# Adafruit_Feather_M0_RFMxx.net
KiCad netlist of a schematic drawn in EAGLE
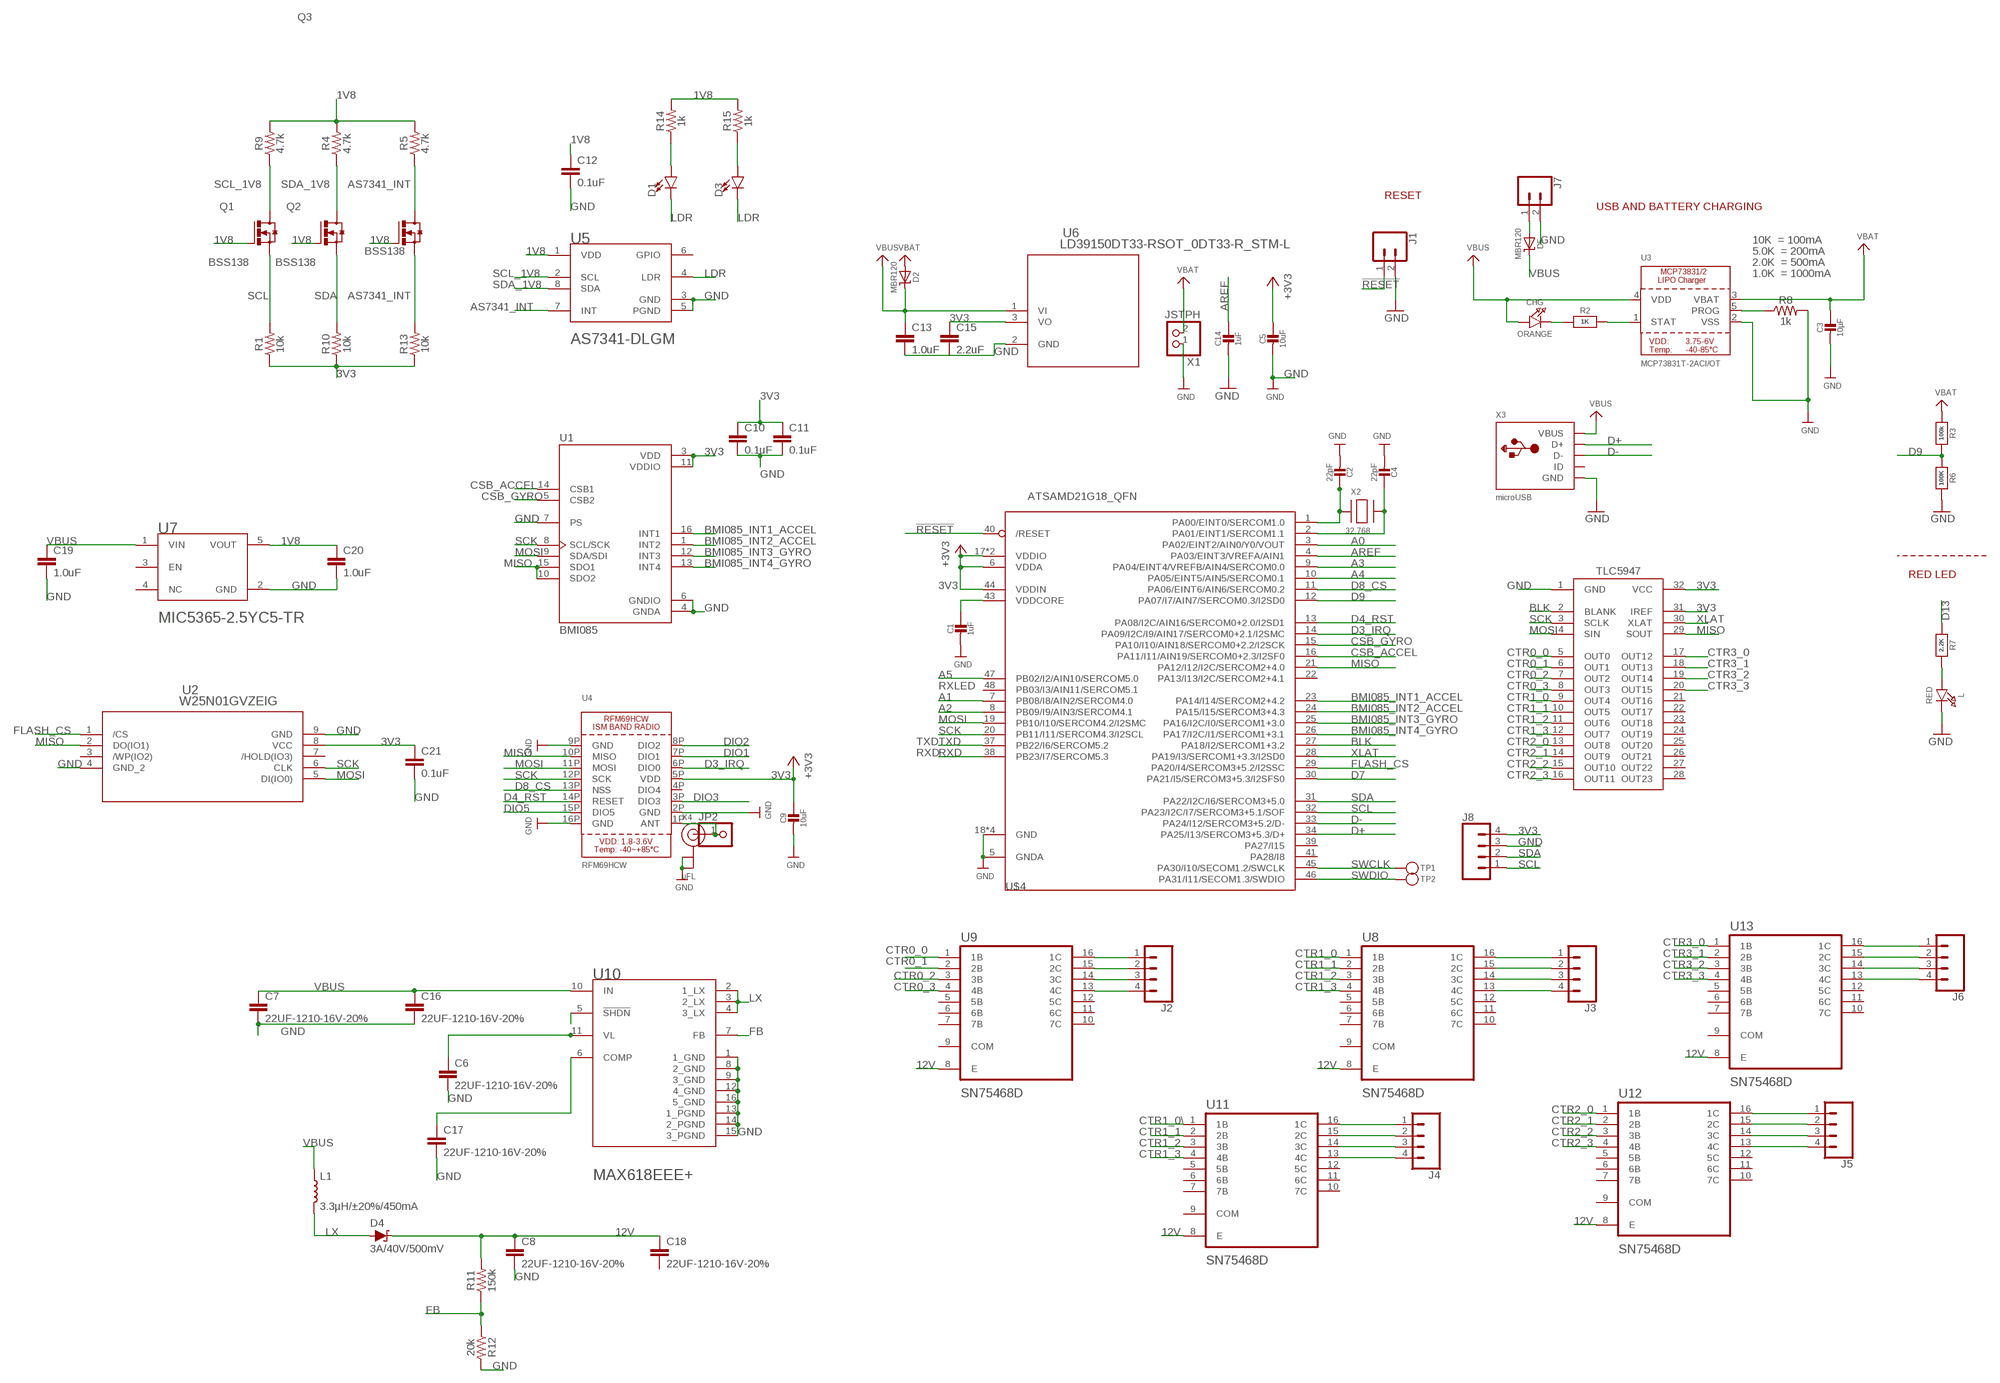
[diagram p0: schematic, sheet 1]

(export (version "E")
  (design (tool "Eeschema 10.0.6"))
  (components
    (comp (ref "C1")
      (value "1uF")
      (footprint "eagle-import:0603-NO")
      (libsource (lib "eagle-import") (part "CAP_CERAMIC0603_NO"))
    )
    (comp (ref "C2")
      (value "22pF")
      (footprint "eagle-import:0603-NO")
      (libsource (lib "eagle-import") (part "CAP_CERAMIC0603_NO"))
    )
    (comp (ref "C3")
      (value "10µF")
      (footprint "eagle-import:0805-NO")
      (libsource (lib "eagle-import") (part "CAP_CERAMIC0805-NOOUTLINE"))
    )
    (comp (ref "C4")
      (value "22pF")
      (footprint "eagle-import:0603-NO")
      (libsource (lib "eagle-import") (part "CAP_CERAMIC0603_NO"))
    )
    (comp (ref "C5")
      (value "10uF")
      (footprint "eagle-import:0805-NO")
      (libsource (lib "eagle-import") (part "CAP_CERAMIC0805-NOOUTLINE"))
    )
    (comp (ref "C6")
      (value "22UF-1210-16V-20%")
      (footprint "eagle-import:1210")
      (libsource (lib "eagle-import") (part "22UF-1210-16V-20%"))
    )
    (comp (ref "C7")
      (value "22UF-1210-16V-20%")
      (footprint "eagle-import:1210")
      (libsource (lib "eagle-import") (part "22UF-1210-16V-20%"))
    )
    (comp (ref "C8")
      (value "22UF-1210-16V-20%")
      (footprint "eagle-import:1210")
      (libsource (lib "eagle-import") (part "22UF-1210-16V-20%"))
    )
    (comp (ref "C9")
      (value "10uF")
      (footprint "eagle-import:0805-NO")
      (libsource (lib "eagle-import") (part "CAP_CERAMIC0805-NOOUTLINE"))
    )
    (comp (ref "C10")
      (value "0.1uF")
      (footprint "eagle-import:0603")
      (libsource (lib "eagle-import") (part "0.1UF-0603-25V-5%"))
    )
    (comp (ref "C11")
      (value "0.1uF")
      (footprint "eagle-import:0603")
      (libsource (lib "eagle-import") (part "0.1UF-0603-25V-5%"))
    )
    (comp (ref "C12")
      (value "0.1uF")
      (footprint "eagle-import:0603")
      (libsource (lib "eagle-import") (part "0.1UF-0603-25V-5%"))
    )
    (comp (ref "C13")
      (value "1.0uF")
      (footprint "eagle-import:0805")
      (libsource (lib "eagle-import") (part "1.0UF-0805-25V-(+80/-20%)"))
    )
    (comp (ref "C14")
      (value "1uF")
      (footprint "eagle-import:0603-NO")
      (libsource (lib "eagle-import") (part "CAP_CERAMIC0603_NO"))
    )
    (comp (ref "C15")
      (value "2.2uF")
      (footprint "eagle-import:0805")
      (libsource (lib "eagle-import") (part "2.2UF-0805-25V-(+80/-20%)"))
    )
    (comp (ref "C16")
      (value "22UF-1210-16V-20%")
      (footprint "eagle-import:1210")
      (libsource (lib "eagle-import") (part "22UF-1210-16V-20%"))
    )
    (comp (ref "C17")
      (value "22UF-1210-16V-20%")
      (footprint "eagle-import:1210")
      (libsource (lib "eagle-import") (part "22UF-1210-16V-20%"))
    )
    (comp (ref "C18")
      (value "22UF-1210-16V-20%")
      (footprint "eagle-import:1210")
      (libsource (lib "eagle-import") (part "22UF-1210-16V-20%"))
    )
    (comp (ref "C19")
      (value "1.0uF")
      (footprint "eagle-import:0805")
      (libsource (lib "eagle-import") (part "1.0UF-0805-25V-(+80/-20%)"))
    )
    (comp (ref "C20")
      (value "1.0uF")
      (footprint "eagle-import:0805")
      (libsource (lib "eagle-import") (part "1.0UF-0805-25V-(+80/-20%)"))
    )
    (comp (ref "C21")
      (value "0.1uF")
      (footprint "eagle-import:0603")
      (libsource (lib "eagle-import") (part "0.1UF-0603-100V-10%"))
    )
    (comp (ref "CHG")
      (value "ORANGE")
      (footprint "eagle-import:CHIPLED_0805_NOOUTLINE")
      (libsource (lib "eagle-import") (part "LED0805_NOOUTLINE"))
    )
    (comp (ref "D1")
      (value "LED1206")
      (footprint "eagle-import:LED-1206")
      (libsource (lib "eagle-import") (part "LED1206"))
    )
    (comp (ref "D2")
      (value "MBR120")
      (footprint "eagle-import:SOD-123")
      (libsource (lib "eagle-import") (part "DIODE-SCHOTTKYSOD-123"))
    )
    (comp (ref "D3")
      (value "LED1206")
      (footprint "eagle-import:LED-1206")
      (libsource (lib "eagle-import") (part "LED1206"))
    )
    (comp (ref "D4")
      (value "3A/40V/500mV")
      (footprint "eagle-import:SMA-DIODE")
      (libsource (lib "eagle-import") (part "DIODE-SCHOTTKY-B340A"))
    )
    (comp (ref "D5")
      (value "MBR120")
      (footprint "eagle-import:SOD-123")
      (libsource (lib "eagle-import") (part "DIODE-SCHOTTKYSOD-123"))
    )
    (comp (ref "IC1")
      (value "TLC5947-DAP")
      (footprint "eagle-import:HTSSOP32DAP")
      (fields (field (name "MF") "Texas Instruments") (field (name "MP") "TLC5947"))
      (libsource (lib "eagle-import") (part "TLC5947-DAP"))
    )
    (comp (ref "J1")
      (value "CONN_02")
      (footprint "eagle-import:1X02")
      (libsource (lib "eagle-import") (part "CONN_02"))
    )
    (comp (ref "J2")
      (value "CONN_04")
      (footprint "eagle-import:1X04")
      (libsource (lib "eagle-import") (part "CONN_04"))
    )
    (comp (ref "J3")
      (value "CONN_04")
      (footprint "eagle-import:1X04")
      (libsource (lib "eagle-import") (part "CONN_04"))
    )
    (comp (ref "J4")
      (value "CONN_04")
      (footprint "eagle-import:1X04")
      (libsource (lib "eagle-import") (part "CONN_04"))
    )
    (comp (ref "J5")
      (value "CONN_04")
      (footprint "eagle-import:1X04")
      (libsource (lib "eagle-import") (part "CONN_04"))
    )
    (comp (ref "J6")
      (value "CONN_04")
      (footprint "eagle-import:1X04")
      (libsource (lib "eagle-import") (part "CONN_04"))
    )
    (comp (ref "J7")
      (value "CONN_02")
      (footprint "eagle-import:1X02")
      (libsource (lib "eagle-import") (part "CONN_02"))
    )
    (comp (ref "J8")
      (value "CONN_04")
      (footprint "eagle-import:1X04")
      (libsource (lib "eagle-import") (part "CONN_04"))
    )
    (comp (ref "JP2")
      (value "HEADER-1X1ROUND")
      (footprint "eagle-import:1X01_ROUND")
      (libsource (lib "eagle-import") (part "HEADER-1X1ROUND"))
    )
    (comp (ref "L")
      (value "RED")
      (footprint "eagle-import:CHIPLED_0805_NOOUTLINE")
      (libsource (lib "eagle-import") (part "LED0805_NOOUTLINE"))
    )
    (comp (ref "L1")
      (value "3.3µH/±20%/450mA")
      (footprint "eagle-import:0805")
      (libsource (lib "eagle-import") (part "INDUCTOR-0805-3.3UH"))
    )
    (comp (ref "Q1")
      (value "BSS138")
      (footprint "eagle-import:SOT23-3")
      (fields
        (field (name "DIGIKEY_PART_NUMBER") "BSS138CT-ND")
        (field (name "MANUFACTURER") "ON Semiconductor")
        (field (name "CREATED_BY") "PCBLayout.com")
      )
      (libsource (lib "eagle-import") (part "BSS138"))
    )
    (comp (ref "Q2")
      (value "BSS138")
      (footprint "eagle-import:SOT23-3")
      (fields
        (field (name "DIGIKEY_PART_NUMBER") "BSS138CT-ND")
        (field (name "MANUFACTURER") "ON Semiconductor")
        (field (name "CREATED_BY") "PCBLayout.com")
      )
      (libsource (lib "eagle-import") (part "BSS138"))
    )
    (comp (ref "Q3")
      (value "BSS138")
      (footprint "eagle-import:SOT23-3")
      (fields
        (field (name "DIGIKEY_PART_NUMBER") "BSS138CT-ND")
        (field (name "MANUFACTURER") "ON Semiconductor")
        (field (name "CREATED_BY") "PCBLayout.com")
      )
      (libsource (lib "eagle-import") (part "BSS138"))
    )
    (comp (ref "R1")
      (value "10k")
      (footprint "eagle-import:0603")
      (libsource (lib "eagle-import") (part "10KOHM-0603-1/10W-1%"))
    )
    (comp (ref "R2")
      (value "1K")
      (footprint "eagle-import:0603-NO")
      (libsource (lib "eagle-import") (part "RESISTOR_0603_NOOUT"))
    )
    (comp (ref "R3")
      (value "100k")
      (footprint "eagle-import:0603-NO")
      (libsource (lib "eagle-import") (part "RESISTOR_0603_NOOUT"))
    )
    (comp (ref "R4")
      (value "4.7k")
      (footprint "eagle-import:0603")
      (libsource (lib "eagle-import") (part "4.7KOHM-0603-1/10W-1%"))
    )
    (comp (ref "R5")
      (value "4.7k")
      (footprint "eagle-import:0603")
      (libsource (lib "eagle-import") (part "4.7KOHM-0603-1/10W-1%"))
    )
    (comp (ref "R6")
      (value "100K")
      (footprint "eagle-import:0603-NO")
      (libsource (lib "eagle-import") (part "RESISTOR_0603_NOOUT"))
    )
    (comp (ref "R7")
      (value "2.2K")
      (footprint "eagle-import:0603-NO")
      (libsource (lib "eagle-import") (part "RESISTOR_0603_NOOUT"))
    )
    (comp (ref "R8")
      (value "1k")
      (footprint "eagle-import:0603")
      (libsource (lib "eagle-import") (part "1KOHM-0603-1/10W-1%"))
    )
    (comp (ref "R9")
      (value "4.7k")
      (footprint "eagle-import:0603")
      (libsource (lib "eagle-import") (part "4.7KOHM-0603-1/10W-1%"))
    )
    (comp (ref "R10")
      (value "10k")
      (footprint "eagle-import:0603")
      (libsource (lib "eagle-import") (part "10KOHM-0603-1/10W-1%"))
    )
    (comp (ref "R11")
      (value "150k")
      (footprint "eagle-import:0603")
      (libsource (lib "eagle-import") (part "150KOHM-0603-1/10W-1%"))
    )
    (comp (ref "R12")
      (value "20k")
      (footprint "eagle-import:0603")
      (libsource (lib "eagle-import") (part "20KOHM-0603-1/10W-1%"))
    )
    (comp (ref "R13")
      (value "10k")
      (footprint "eagle-import:0603")
      (libsource (lib "eagle-import") (part "10KOHM-0603-1/10W-1%"))
    )
    (comp (ref "R14")
      (value "1k")
      (footprint "eagle-import:0603")
      (libsource (lib "eagle-import") (part "1KOHM-0603-1/10W-1%"))
    )
    (comp (ref "R15")
      (value "1k")
      (footprint "eagle-import:0603")
      (libsource (lib "eagle-import") (part "1KOHM-0603-1/10W-1%"))
    )
    (comp (ref "TP1")
      (value "TESTPOINTROUND1.5MM")
      (footprint "eagle-import:TESTPOINT_ROUND_1.5MM")
      (libsource (lib "eagle-import") (part "TESTPOINTROUND1.5MM"))
    )
    (comp (ref "TP2")
      (value "TESTPOINTROUND1.5MM")
      (footprint "eagle-import:TESTPOINT_ROUND_1.5MM")
      (libsource (lib "eagle-import") (part "TESTPOINTROUND1.5MM"))
    )
    (comp (ref "U$4")
      (value "ATSAMD21G18_QFN")
      (footprint "eagle-import:TQFN48_7MM")
      (libsource (lib "eagle-import") (part "ATSAMD21J_QFN"))
    )
    (comp (ref "U1")
      (value "BMI085")
      (footprint "eagle-import:PQFN50P450X300X100-16N")
      (fields (field (name "MF") "Bosch Sensortec"))
      (libsource (lib "eagle-import") (part "BMI085"))
    )
    (comp (ref "U2")
      (value "W25N01GVZEIG")
      (footprint "eagle-import:WSON-8_6X5_WIN")
      (fields (field (name "COPYRIGHT") "Copyright (C) 2021 Ultra Librarian. All rights reserved."))
      (libsource (lib "eagle-import") (part "W25N01GVZEIG"))
    )
    (comp (ref "U3")
      (value "MCP73831T-2ACI/OT")
      (footprint "eagle-import:SOT23-5")
      (libsource (lib "eagle-import") (part "MCP73831/2"))
    )
    (comp (ref "U4")
      (value "RFM69HCW")
      (footprint "eagle-import:RFMHCW_SMT")
      (libsource (lib "eagle-import") (part "RFM69HCW_SMT"))
    )
    (comp (ref "U5")
      (value "AMS_AS7341-DLGMAMS_AS7341-DLGM_0_0")
      (footprint "eagle-import:AMS_AS7341-DLGM_0")
      (fields
        (field (name "DIGIKEY_PART_NUMBER") "AS7341-DLGMCT-ND")
        (field (name "MF") "ams")
        (field (name "MOUSER_PART_NUMBER") "985-AS7341-DLGM")
      )
      (libsource (lib "eagle-import") (part "AMS_AS7341-DLGMAMS_AS7341-DLGM_0_0"))
    )
    (comp (ref "U6")
      (value "LD39150DT33-RSOT_0DT33-R_STM-L")
      (footprint "eagle-import:SOT_0DT33-R_STM-L")
      (fields
        (field (name "MANUFACTURER_PART_NUMBER") "LD39150DT33-R")
        (field (name "COPYRIGHT") "Copyright (C) 2022 Ultra Librarian. All rights reserved.")
      )
      (libsource (lib "eagle-import") (part "LD39150DT33-RSOT_0DT33-R_STM-L"))
    )
    (comp (ref "U7")
      (value "MICROCHIP_MIC5365-2_5YC5-TRMICROCHIP_MIC5365-2_5YC5-TR_0_0")
      (footprint "eagle-import:MICROCHIP_MIC5365-2_5YC5-TR_0")
      (fields
        (field (name "DIGIKEY_PART_NUMBER") "576-3185-1-ND")
        (field (name "MF") "Microchip")
        (field (name "MOUSER_PART_NUMBER") "998-MIC5365-2.5YC5TR")
      )
      (libsource (lib "eagle-import") (part "MICROCHIP_MIC5365-2_5YC5-TRMICROCHIP_MIC5365-2_5YC5-TR_0_0"))
    )
    (comp (ref "U8")
      (value "SN75468D")
      (footprint "eagle-import:SOIC127P600X175-16N")
      (fields (field (name "MF") "Texas Instruments"))
      (libsource (lib "eagle-import") (part "SN75468D"))
    )
    (comp (ref "U9")
      (value "SN75468D")
      (footprint "eagle-import:SOIC127P600X175-16N")
      (fields (field (name "MF") "Texas Instruments"))
      (libsource (lib "eagle-import") (part "SN75468D"))
    )
    (comp (ref "U10")
      (value "MAXIM_MAX618EEE+MAXIM_MAX618EEE+_0_0")
      (footprint "eagle-import:MAXIM_MAX618EEE+_0")
      (fields
        (field (name "DIGIKEY_PART_NUMBER") "MAX618EEE+-ND")
        (field (name "MF") "Maxim")
        (field (name "MOUSER_PART_NUMBER") "700-MAX618EEE")
      )
      (libsource (lib "eagle-import") (part "MAXIM_MAX618EEE+MAXIM_MAX618EEE+_0_0"))
    )
    (comp (ref "U11")
      (value "SN75468D")
      (footprint "eagle-import:SOIC127P600X175-16N")
      (fields (field (name "MF") "Texas Instruments"))
      (libsource (lib "eagle-import") (part "SN75468D"))
    )
    (comp (ref "U12")
      (value "SN75468D")
      (footprint "eagle-import:SOIC127P600X175-16N")
      (fields (field (name "MF") "Texas Instruments"))
      (libsource (lib "eagle-import") (part "SN75468D"))
    )
    (comp (ref "U13")
      (value "SN75468D")
      (footprint "eagle-import:SOIC127P600X175-16N")
      (fields (field (name "MF") "Texas Instruments"))
      (libsource (lib "eagle-import") (part "SN75468D"))
    )
    (comp (ref "X1")
      (value "JSTPH")
      (footprint "eagle-import:JSTPH2")
      (libsource (lib "eagle-import") (part "CON_JST_PH_2PIN"))
    )
    (comp (ref "X2")
      (value "32.768")
      (footprint "eagle-import:XTAL3215")
      (libsource (lib "eagle-import") (part "XTAL-3.2X1.5"))
    )
    (comp (ref "X3")
      (value "microUSB")
      (footprint "eagle-import:4UCONN_20329_V2")
      (libsource (lib "eagle-import") (part "USB_MICRO_20329_V2"))
    )
    (comp (ref "X4")
      (value "uFL")
      (footprint "eagle-import:U.FL")
      (libsource (lib "eagle-import") (part "ANTENNA_U.FL"))
    )
  )
  (nets
    (net (code "1") (name "+3V3") (class "Default")
      (node (ref "C10") (pin "1") (pinfunction "1_1") (pintype "passive"))
      (node (ref "C11") (pin "1") (pinfunction "1_1") (pintype "passive"))
      (node (ref "C15") (pin "1") (pinfunction "1_1") (pintype "passive"))
      (node (ref "C21") (pin "1") (pinfunction "1_1") (pintype "passive"))
      (node (ref "C5") (pin "1") (pinfunction "1_1") (pintype "passive"))
      (node (ref "C9") (pin "1") (pinfunction "1_1") (pintype "passive"))
      (node (ref "IC1") (pin "31") (pinfunction "IREF_31") (pintype "bidirectional"))
      (node (ref "IC1") (pin "32") (pinfunction "VCC_32") (pintype "power_in"))
      (node (ref "J8") (pin "4") (pinfunction "4_4") (pintype "passive"))
      (node (ref "R1") (pin "1") (pinfunction "1_1") (pintype "passive"))
      (node (ref "R10") (pin "1") (pinfunction "1_1") (pintype "passive"))
      (node (ref "R13") (pin "1") (pinfunction "1_1") (pintype "passive"))
      (node (ref "U$4") (pin "17") (pinfunction "VDDIO_17") (pintype "power_in"))
      (node (ref "U$4") (pin "36") (pinfunction "VDDIO_36") (pintype "power_in"))
      (node (ref "U$4") (pin "44") (pinfunction "VDDIN_44") (pintype "power_in"))
      (node (ref "U$4") (pin "6") (pinfunction "VDDA_6") (pintype "power_in"))
      (node (ref "U1") (pin "11") (pinfunction "VDDIO_11") (pintype "power_in"))
      (node (ref "U1") (pin "3") (pinfunction "VDD_3") (pintype "power_in"))
      (node (ref "U2") (pin "8") (pinfunction "VCC_8") (pintype "power_in"))
      (node (ref "U4") (pin "5P") (pinfunction "VDD_5P") (pintype "power_in"))
      (node (ref "U6") (pin "3") (pinfunction "VO_3") (pintype "power_in"))
    )
    (net (code "2") (name "/1V8") (class "Default")
      (node (ref "C12") (pin "1") (pinfunction "1_1") (pintype "passive"))
      (node (ref "C20") (pin "1") (pinfunction "1_1") (pintype "passive"))
      (node (ref "Q1") (pin "1") (pinfunction "G_1") (pintype "passive"))
      (node (ref "Q2") (pin "1") (pinfunction "G_1") (pintype "passive"))
      (node (ref "Q3") (pin "1") (pinfunction "G_1") (pintype "passive"))
      (node (ref "R14") (pin "2") (pinfunction "2_2") (pintype "passive"))
      (node (ref "R15") (pin "2") (pinfunction "2_2") (pintype "passive"))
      (node (ref "R4") (pin "2") (pinfunction "2_2") (pintype "passive"))
      (node (ref "R5") (pin "2") (pinfunction "2_2") (pintype "passive"))
      (node (ref "R9") (pin "2") (pinfunction "2_2") (pintype "passive"))
      (node (ref "U5") (pin "1") (pinfunction "VDD_1") (pintype "power_in"))
      (node (ref "U7") (pin "5") (pinfunction "VOUT_5") (pintype "power_in"))
    )
    (net (code "3") (name "/12V") (class "Default")
      (node (ref "C18") (pin "1") (pinfunction "1_1") (pintype "passive"))
      (node (ref "C8") (pin "1") (pinfunction "1_1") (pintype "passive"))
      (node (ref "D4") (pin "C") (pinfunction "C_C") (pintype "passive"))
      (node (ref "R11") (pin "2") (pinfunction "2_2") (pintype "passive"))
      (node (ref "U11") (pin "8") (pinfunction "E_8") (pintype "bidirectional"))
      (node (ref "U12") (pin "8") (pinfunction "E_8") (pintype "bidirectional"))
      (node (ref "U13") (pin "8") (pinfunction "E_8") (pintype "bidirectional"))
      (node (ref "U8") (pin "8") (pinfunction "E_8") (pintype "bidirectional"))
      (node (ref "U9") (pin "8") (pinfunction "E_8") (pintype "bidirectional"))
    )
    (net (code "4") (name "/A0") (class "Default")
      (node (ref "U$4") (pin "3") (pinfunction "PA02/EINT2/AIN0/Y0/VOUT_3") (pintype "bidirectional"))
    )
    (net (code "5") (name "/A1") (class "Default")
      (node (ref "U$4") (pin "7") (pinfunction "PB08/I8/AIN2/SERCOM4.0_7") (pintype "bidirectional"))
    )
    (net (code "6") (name "/A2") (class "Default")
      (node (ref "U$4") (pin "8") (pinfunction "PB09/I9/AIN3/SERCOM4.1_8") (pintype "bidirectional"))
    )
    (net (code "7") (name "/A3") (class "Default")
      (node (ref "U$4") (pin "9") (pinfunction "PA04/EINT4/VREFB/AIN4/SERCOM0.0_9") (pintype "bidirectional"))
    )
    (net (code "8") (name "/A4") (class "Default")
      (node (ref "U$4") (pin "10") (pinfunction "PA05/EINT5/AIN5/SERCOM0.1_10") (pintype "bidirectional"))
    )
    (net (code "9") (name "/A5") (class "Default")
      (node (ref "U$4") (pin "47") (pinfunction "PB02/I2/AIN10/SERCOM5.0_47") (pintype "bidirectional"))
    )
    (net (code "10") (name "/AREF") (class "Default")
      (node (ref "C14") (pin "1") (pinfunction "1_1") (pintype "passive"))
      (node (ref "U$4") (pin "4") (pinfunction "PA03/EINT3/VREFA/AIN1_4") (pintype "bidirectional"))
    )
    (net (code "11") (name "/AS7341_INT") (class "Default")
      (node (ref "Q3") (pin "2") (pinfunction "S_2") (pintype "passive"))
      (node (ref "Q3") (pin "3") (pinfunction "D_3") (pintype "passive"))
      (node (ref "R13") (pin "2") (pinfunction "2_2") (pintype "passive"))
      (node (ref "R5") (pin "1") (pinfunction "1_1") (pintype "passive"))
      (node (ref "U5") (pin "7") (pinfunction "INT_7") (pintype "output"))
    )
    (net (code "12") (name "/BLK") (class "Default")
      (node (ref "IC1") (pin "2") (pinfunction "BLANK_2") (pintype "input"))
      (node (ref "U$4") (pin "27") (pinfunction "PA18/I2/SERCOM1+3.2_27") (pintype "bidirectional"))
    )
    (net (code "13") (name "/BMI085_INT1_ACCEL") (class "Default")
      (node (ref "U$4") (pin "23") (pinfunction "PA14/I14/SERCOM2+4.2_23") (pintype "bidirectional"))
      (node (ref "U1") (pin "16") (pinfunction "INT1_16") (pintype "bidirectional"))
    )
    (net (code "14") (name "/BMI085_INT2_ACCEL") (class "Default")
      (node (ref "U$4") (pin "24") (pinfunction "PA15/I15/SERCOM3+4.3_24") (pintype "bidirectional"))
      (node (ref "U1") (pin "1") (pinfunction "INT2_1") (pintype "bidirectional"))
    )
    (net (code "15") (name "/BMI085_INT3_GYRO") (class "Default")
      (node (ref "U$4") (pin "25") (pinfunction "PA16/I2C/I0/SERCOM1+3.0_25") (pintype "bidirectional"))
      (node (ref "U1") (pin "12") (pinfunction "INT3_12") (pintype "bidirectional"))
    )
    (net (code "16") (name "/BMI085_INT4_GYRO") (class "Default")
      (node (ref "U$4") (pin "26") (pinfunction "PA17/I2C/I1/SERCOM1+3.1_26") (pintype "bidirectional"))
      (node (ref "U1") (pin "13") (pinfunction "INT4_13") (pintype "bidirectional"))
    )
    (net (code "17") (name "/CSB_ACCEL") (class "Default")
      (node (ref "U$4") (pin "16") (pinfunction "PA11/I11/AIN19/SERCOM0+2.3/I2SF0_16") (pintype "bidirectional"))
      (node (ref "U1") (pin "14") (pinfunction "CSB1_14") (pintype "input"))
    )
    (net (code "18") (name "/CSB_GYRO") (class "Default")
      (node (ref "U$4") (pin "15") (pinfunction "PA10/I10/AIN18/SERCOM0+2.2/I2SCK_15") (pintype "bidirectional"))
      (node (ref "U1") (pin "5") (pinfunction "CSB2_5") (pintype "input"))
    )
    (net (code "19") (name "/CTR0_0") (class "Default")
      (node (ref "IC1") (pin "5") (pinfunction "OUT0_5") (pintype "open_collector"))
      (node (ref "U9") (pin "1") (pinfunction "1B_1") (pintype "input"))
    )
    (net (code "20") (name "/CTR0_1") (class "Default")
      (node (ref "IC1") (pin "6") (pinfunction "OUT1_6") (pintype "open_collector"))
      (node (ref "U9") (pin "2") (pinfunction "2B_2") (pintype "input"))
    )
    (net (code "21") (name "/CTR0_2") (class "Default")
      (node (ref "IC1") (pin "7") (pinfunction "OUT2_7") (pintype "open_collector"))
      (node (ref "U9") (pin "3") (pinfunction "3B_3") (pintype "input"))
    )
    (net (code "22") (name "/CTR0_3") (class "Default")
      (node (ref "IC1") (pin "8") (pinfunction "OUT3_8") (pintype "open_collector"))
      (node (ref "U9") (pin "4") (pinfunction "4B_4") (pintype "input"))
    )
    (net (code "23") (name "/CTR1_0") (class "Default")
      (node (ref "IC1") (pin "9") (pinfunction "OUT4_9") (pintype "open_collector"))
      (node (ref "U8") (pin "1") (pinfunction "1B_1") (pintype "input"))
    )
    (net (code "24") (name "/CTR1_0\\") (class "Default")
      (node (ref "U11") (pin "1") (pinfunction "1B_1") (pintype "input"))
    )
    (net (code "25") (name "/CTR1_1") (class "Default")
      (node (ref "IC1") (pin "10") (pinfunction "OUT5_10") (pintype "open_collector"))
      (node (ref "U11") (pin "2") (pinfunction "2B_2") (pintype "input"))
      (node (ref "U8") (pin "2") (pinfunction "2B_2") (pintype "input"))
    )
    (net (code "26") (name "/CTR1_2") (class "Default")
      (node (ref "IC1") (pin "11") (pinfunction "OUT6_11") (pintype "open_collector"))
      (node (ref "U11") (pin "3") (pinfunction "3B_3") (pintype "input"))
      (node (ref "U8") (pin "3") (pinfunction "3B_3") (pintype "input"))
    )
    (net (code "27") (name "/CTR1_3") (class "Default")
      (node (ref "IC1") (pin "12") (pinfunction "OUT7_12") (pintype "open_collector"))
      (node (ref "U11") (pin "4") (pinfunction "4B_4") (pintype "input"))
      (node (ref "U8") (pin "4") (pinfunction "4B_4") (pintype "input"))
    )
    (net (code "28") (name "/CTR2_0") (class "Default")
      (node (ref "IC1") (pin "13") (pinfunction "OUT8_13") (pintype "open_collector"))
      (node (ref "U12") (pin "1") (pinfunction "1B_1") (pintype "input"))
    )
    (net (code "29") (name "/CTR2_1") (class "Default")
      (node (ref "IC1") (pin "14") (pinfunction "OUT9_14") (pintype "open_collector"))
      (node (ref "U12") (pin "2") (pinfunction "2B_2") (pintype "input"))
    )
    (net (code "30") (name "/CTR2_2") (class "Default")
      (node (ref "IC1") (pin "15") (pinfunction "OUT10_15") (pintype "open_collector"))
      (node (ref "U12") (pin "3") (pinfunction "3B_3") (pintype "input"))
    )
    (net (code "31") (name "/CTR2_3") (class "Default")
      (node (ref "IC1") (pin "16") (pinfunction "OUT11_16") (pintype "open_collector"))
      (node (ref "U12") (pin "4") (pinfunction "4B_4") (pintype "input"))
    )
    (net (code "32") (name "/CTR3_0") (class "Default")
      (node (ref "IC1") (pin "17") (pinfunction "OUT12_17") (pintype "open_collector"))
      (node (ref "U13") (pin "1") (pinfunction "1B_1") (pintype "input"))
    )
    (net (code "33") (name "/CTR3_1") (class "Default")
      (node (ref "IC1") (pin "18") (pinfunction "OUT13_18") (pintype "open_collector"))
      (node (ref "U13") (pin "2") (pinfunction "2B_2") (pintype "input"))
    )
    (net (code "34") (name "/CTR3_2") (class "Default")
      (node (ref "IC1") (pin "19") (pinfunction "OUT14_19") (pintype "open_collector"))
      (node (ref "U13") (pin "3") (pinfunction "3B_3") (pintype "input"))
    )
    (net (code "35") (name "/CTR3_3") (class "Default")
      (node (ref "IC1") (pin "20") (pinfunction "OUT15_20") (pintype "open_collector"))
      (node (ref "U13") (pin "4") (pinfunction "4B_4") (pintype "input"))
    )
    (net (code "36") (name "/D+") (class "Default")
      (node (ref "U$4") (pin "34") (pinfunction "PA25/I13/SERCOM3+5.3/D+_34") (pintype "bidirectional"))
      (node (ref "X3") (pin "D+") (pinfunction "D+_D+") (pintype "bidirectional"))
    )
    (net (code "37") (name "/D-") (class "Default")
      (node (ref "U$4") (pin "33") (pinfunction "PA24/I12/SERCOM3+5.2/D-_33") (pintype "bidirectional"))
      (node (ref "X3") (pin "D-") (pinfunction "D-_D-") (pintype "bidirectional"))
    )
    (net (code "38") (name "/D3_IRQ") (class "Default")
      (node (ref "U$4") (pin "14") (pinfunction "PA09/I2C/I9/AIN17/SERCOM0+2.1/I2SMC_14") (pintype "bidirectional"))
      (node (ref "U4") (pin "6P") (pinfunction "DIO0_6P") (pintype "bidirectional"))
    )
    (net (code "39") (name "/D4_RST") (class "Default")
      (node (ref "U$4") (pin "13") (pinfunction "PA08/I2C/AIN16/SERCOM0+2.0/I2SD1_13") (pintype "bidirectional"))
      (node (ref "U4") (pin "14P") (pinfunction "RESET_14P") (pintype "input"))
    )
    (net (code "40") (name "/D7") (class "Default")
      (node (ref "U$4") (pin "30") (pinfunction "PA21/I5/SERCOM3+5.3/I2SFS0_30") (pintype "bidirectional"))
    )
    (net (code "41") (name "/D8_CS") (class "Default")
      (node (ref "U$4") (pin "11") (pinfunction "PA06/EINT6/AIN6/SERCOM0.2_11") (pintype "bidirectional"))
      (node (ref "U4") (pin "13P") (pinfunction "NSS_13P") (pintype "input"))
    )
    (net (code "42") (name "/D9") (class "Default")
      (node (ref "R3") (pin "2") (pinfunction "2_2") (pintype "passive"))
      (node (ref "R6") (pin "1") (pinfunction "1_1") (pintype "passive"))
      (node (ref "U$4") (pin "12") (pinfunction "PA07/I7/AIN7/SERCOM0.3/I2SD0_12") (pintype "bidirectional"))
    )
    (net (code "43") (name "/D13") (class "Default")
      (node (ref "R7") (pin "1") (pinfunction "1_1") (pintype "passive"))
    )
    (net (code "44") (name "/DIO1") (class "Default")
      (node (ref "U4") (pin "7P") (pinfunction "DIO1_7P") (pintype "bidirectional"))
    )
    (net (code "45") (name "/DIO2") (class "Default")
      (node (ref "U4") (pin "8P") (pinfunction "DIO2_8P") (pintype "bidirectional"))
    )
    (net (code "46") (name "/DIO3") (class "Default")
      (node (ref "U4") (pin "3P") (pinfunction "DIO3_3P") (pintype "bidirectional"))
    )
    (net (code "47") (name "/DIO5") (class "Default")
      (node (ref "U4") (pin "15P") (pinfunction "DIO5_15P") (pintype "bidirectional"))
    )
    (net (code "48") (name "/FB") (class "Default")
      (node (ref "R11") (pin "1") (pinfunction "1_1") (pintype "passive"))
      (node (ref "R12") (pin "1") (pinfunction "1_1") (pintype "passive"))
      (node (ref "U10") (pin "7") (pinfunction "FB_7") (pintype "passive"))
    )
    (net (code "49") (name "/FLASH_CS") (class "Default")
      (node (ref "U$4") (pin "29") (pinfunction "PA20/I4/SERCOM3+5.2/I2SSC_29") (pintype "bidirectional"))
      (node (ref "U2") (pin "1") (pinfunction "/CS_1") (pintype "input"))
    )
    (net (code "50") (name "/LDR") (class "Default")
      (node (ref "D1") (pin "C") (pinfunction "C_C") (pintype "passive"))
      (node (ref "D3") (pin "C") (pinfunction "C_C") (pintype "passive"))
      (node (ref "U5") (pin "4") (pinfunction "LDR_4") (pintype "input"))
    )
    (net (code "51") (name "/LX") (class "Default")
      (node (ref "D4") (pin "A") (pinfunction "A_A") (pintype "passive"))
      (node (ref "L1") (pin "2") (pinfunction "2_2") (pintype "passive"))
      (node (ref "U10") (pin "2") (pinfunction "1_LX_2") (pintype "passive"))
      (node (ref "U10") (pin "3") (pinfunction "2_LX_3") (pintype "passive"))
      (node (ref "U10") (pin "4") (pinfunction "3_LX_4") (pintype "passive"))
    )
    (net (code "52") (name "/MISO") (class "Default")
      (node (ref "IC1") (pin "29") (pinfunction "SOUT_29") (pintype "output"))
      (node (ref "U$4") (pin "21") (pinfunction "PA12/I12/I2C/SERCOM2+4.0_21") (pintype "bidirectional"))
      (node (ref "U1") (pin "10") (pinfunction "SDO2_10") (pintype "output"))
      (node (ref "U1") (pin "15") (pinfunction "SDO1_15") (pintype "output"))
      (node (ref "U2") (pin "2") (pinfunction "DO(IO1)_2") (pintype "bidirectional"))
      (node (ref "U4") (pin "10P") (pinfunction "MISO_10P") (pintype "output"))
    )
    (net (code "53") (name "/MOSI") (class "Default")
      (node (ref "IC1") (pin "4") (pinfunction "SIN_4") (pintype "input"))
      (node (ref "U$4") (pin "19") (pinfunction "PB10/I10/SERCOM4.2/I2SMC_19") (pintype "bidirectional"))
      (node (ref "U1") (pin "9") (pinfunction "SDA/SDI_9") (pintype "bidirectional"))
      (node (ref "U2") (pin "5") (pinfunction "DI(IO0)_5") (pintype "bidirectional"))
      (node (ref "U4") (pin "11P") (pinfunction "MOSI_11P") (pintype "input"))
    )
    (net (code "54") (name "/RXD") (class "Default")
      (node (ref "U$4") (pin "38") (pinfunction "PB23/I7/SERCOM5.3_38") (pintype "bidirectional"))
    )
    (net (code "55") (name "/SCK") (class "Default")
      (node (ref "IC1") (pin "3") (pinfunction "SCLK_3") (pintype "input"))
      (node (ref "U$4") (pin "20") (pinfunction "PB11/I11/SERCOM4.3/I2SCL_20") (pintype "bidirectional"))
      (node (ref "U1") (pin "8") (pinfunction "SCL/SCK_8") (pintype "input"))
      (node (ref "U2") (pin "6") (pinfunction "CLK_6") (pintype "input"))
      (node (ref "U4") (pin "12P") (pinfunction "SCK_12P") (pintype "input"))
    )
    (net (code "56") (name "/SCL") (class "Default")
      (node (ref "J8") (pin "1") (pinfunction "1_1") (pintype "passive"))
      (node (ref "Q1") (pin "2") (pinfunction "S_2") (pintype "passive"))
      (node (ref "R1") (pin "2") (pinfunction "2_2") (pintype "passive"))
      (node (ref "U$4") (pin "32") (pinfunction "PA23/I2C/I7/SERCOM3+5.1/SOF_32") (pintype "bidirectional"))
    )
    (net (code "57") (name "/SCL_1V8") (class "Default")
      (node (ref "Q1") (pin "3") (pinfunction "D_3") (pintype "passive"))
      (node (ref "R9") (pin "1") (pinfunction "1_1") (pintype "passive"))
      (node (ref "U5") (pin "2") (pinfunction "SCL_2") (pintype "bidirectional"))
    )
    (net (code "58") (name "/SDA") (class "Default")
      (node (ref "J8") (pin "2") (pinfunction "2_2") (pintype "passive"))
      (node (ref "Q2") (pin "2") (pinfunction "S_2") (pintype "passive"))
      (node (ref "R10") (pin "2") (pinfunction "2_2") (pintype "passive"))
      (node (ref "U$4") (pin "31") (pinfunction "PA22/I2C/I6/SERCOM3+5.0_31") (pintype "bidirectional"))
    )
    (net (code "59") (name "/SDA_1V8") (class "Default")
      (node (ref "Q2") (pin "3") (pinfunction "D_3") (pintype "passive"))
      (node (ref "R4") (pin "1") (pinfunction "1_1") (pintype "passive"))
      (node (ref "U5") (pin "8") (pinfunction "SDA_8") (pintype "bidirectional"))
    )
    (net (code "60") (name "/SWCLK") (class "Default")
      (node (ref "TP1") (pin "P$1") (pinfunction "P$1_P$1") (pintype "bidirectional"))
      (node (ref "U$4") (pin "45") (pinfunction "PA30/I10/SECOM1.2/SWCLK_45") (pintype "bidirectional"))
    )
    (net (code "61") (name "/SWDIO") (class "Default")
      (node (ref "TP2") (pin "P$1") (pinfunction "P$1_P$1") (pintype "bidirectional"))
      (node (ref "U$4") (pin "46") (pinfunction "PA31/I11/SECOM1.3/SWDIO_46") (pintype "bidirectional"))
    )
    (net (code "62") (name "/TXD") (class "Default")
      (node (ref "U$4") (pin "37") (pinfunction "PB22/I6/SERCOM5.2_37") (pintype "bidirectional"))
    )
    (net (code "63") (name "/XLAT") (class "Default")
      (node (ref "IC1") (pin "30") (pinfunction "XLAT_30") (pintype "input"))
      (node (ref "U$4") (pin "28") (pinfunction "PA19/I3/SERCOM1+3.3/I2SD0_28") (pintype "bidirectional"))
    )
    (net (code "64") (name "/~{RESET}") (class "Default")
      (node (ref "J1") (pin "1") (pinfunction "1_1") (pintype "passive"))
      (node (ref "U$4") (pin "40") (pinfunction "/RESET_40") (pintype "bidirectional"))
    )
    (net (code "65") (name "GND") (class "Default")
      (node (ref "C1") (pin "2") (pinfunction "2_2") (pintype "passive"))
      (node (ref "C10") (pin "2") (pinfunction "2_2") (pintype "passive"))
      (node (ref "C11") (pin "2") (pinfunction "2_2") (pintype "passive"))
      (node (ref "C12") (pin "2") (pinfunction "2_2") (pintype "passive"))
      (node (ref "C13") (pin "2") (pinfunction "2_2") (pintype "passive"))
      (node (ref "C14") (pin "2") (pinfunction "2_2") (pintype "passive"))
      (node (ref "C15") (pin "2") (pinfunction "2_2") (pintype "passive"))
      (node (ref "C16") (pin "2") (pinfunction "2_2") (pintype "passive"))
      (node (ref "C17") (pin "2") (pinfunction "2_2") (pintype "passive"))
      (node (ref "C19") (pin "2") (pinfunction "2_2") (pintype "passive"))
      (node (ref "C2") (pin "2") (pinfunction "2_2") (pintype "passive"))
      (node (ref "C20") (pin "2") (pinfunction "2_2") (pintype "passive"))
      (node (ref "C21") (pin "2") (pinfunction "2_2") (pintype "passive"))
      (node (ref "C3") (pin "2") (pinfunction "2_2") (pintype "passive"))
      (node (ref "C4") (pin "2") (pinfunction "2_2") (pintype "passive"))
      (node (ref "C5") (pin "2") (pinfunction "2_2") (pintype "passive"))
      (node (ref "C6") (pin "2") (pinfunction "2_2") (pintype "passive"))
      (node (ref "C7") (pin "2") (pinfunction "2_2") (pintype "passive"))
      (node (ref "C8") (pin "2") (pinfunction "2_2") (pintype "passive"))
      (node (ref "C9") (pin "2") (pinfunction "2_2") (pintype "passive"))
      (node (ref "IC1") (pin "1") (pinfunction "GND_1") (pintype "power_in"))
      (node (ref "J1") (pin "2") (pinfunction "2_2") (pintype "passive"))
      (node (ref "J7") (pin "2") (pinfunction "2_2") (pintype "passive"))
      (node (ref "J8") (pin "3") (pinfunction "3_3") (pintype "passive"))
      (node (ref "L") (pin "C") (pinfunction "C_C") (pintype "passive"))
      (node (ref "R12") (pin "2") (pinfunction "2_2") (pintype "passive"))
      (node (ref "R6") (pin "2") (pinfunction "2_2") (pintype "passive"))
      (node (ref "R8") (pin "2") (pinfunction "2_2") (pintype "passive"))
      (node (ref "U$4") (pin "18") (pinfunction "GND_18") (pintype "power_in"))
      (node (ref "U$4") (pin "35") (pinfunction "GND_35") (pintype "power_in"))
      (node (ref "U$4") (pin "42") (pinfunction "GND_42") (pintype "power_in"))
      (node (ref "U$4") (pin "5") (pinfunction "GNDA_5") (pintype "power_in"))
      (node (ref "U$4") (pin "THERMAL") (pinfunction "GND_THERMAL") (pintype "power_in"))
      (node (ref "U1") (pin "4") (pinfunction "GNDA_4") (pintype "power_in"))
      (node (ref "U1") (pin "6") (pinfunction "GNDIO_6") (pintype "power_in"))
      (node (ref "U1") (pin "7") (pinfunction "PS_7") (pintype "input"))
      (node (ref "U10") (pin "1") (pinfunction "1_GND_1") (pintype "power_in"))
      (node (ref "U10") (pin "12") (pinfunction "4_GND_12") (pintype "power_in"))
      (node (ref "U10") (pin "13") (pinfunction "1_PGND_13") (pintype "power_in"))
      (node (ref "U10") (pin "14") (pinfunction "2_PGND_14") (pintype "power_in"))
      (node (ref "U10") (pin "15") (pinfunction "3_PGND_15") (pintype "power_in"))
      (node (ref "U10") (pin "16") (pinfunction "5_GND_16") (pintype "power_in"))
      (node (ref "U10") (pin "8") (pinfunction "2_GND_8") (pintype "power_in"))
      (node (ref "U10") (pin "9") (pinfunction "3_GND_9") (pintype "power_in"))
      (node (ref "U2") (pin "4") (pinfunction "GND_2_4") (pintype "passive"))
      (node (ref "U2") (pin "9") (pinfunction "GND_9") (pintype "passive"))
      (node (ref "U3") (pin "2") (pinfunction "VSS_2") (pintype "power_in"))
      (node (ref "U4") (pin "16P") (pinfunction "GND_16P") (pintype "power_in"))
      (node (ref "U4") (pin "2P") (pinfunction "GND_2P") (pintype "power_in"))
      (node (ref "U4") (pin "9P") (pinfunction "GND_9P") (pintype "power_in"))
      (node (ref "U5") (pin "3") (pinfunction "GND_3") (pintype "power_in"))
      (node (ref "U5") (pin "5") (pinfunction "PGND_5") (pintype "power_in"))
      (node (ref "U6") (pin "2") (pinfunction "GND_2") (pintype "passive"))
      (node (ref "U7") (pin "2") (pinfunction "GND_2") (pintype "power_in"))
      (node (ref "X1") (pin "1") (pinfunction "1_1") (pintype "passive"))
      (node (ref "X3") (pin "BASE@1") (pinfunction "GND_BASE@1") (pintype "power_in"))
      (node (ref "X3") (pin "BASE@2") (pinfunction "GND_BASE@2") (pintype "power_in"))
      (node (ref "X3") (pin "GND") (pinfunction "GND_GND") (pintype "power_in"))
      (node (ref "X3") (pin "SPRT@1") (pinfunction "GND_SPRT@1") (pintype "power_in"))
      (node (ref "X3") (pin "SPRT@2") (pinfunction "GND_SPRT@2") (pintype "power_in"))
      (node (ref "X3") (pin "SPRT@3") (pinfunction "GND_SPRT@3") (pintype "power_in"))
      (node (ref "X3") (pin "SPRT@4") (pinfunction "GND_SPRT@4") (pintype "power_in"))
      (node (ref "X4") (pin "1") (pinfunction "GND_1") (pintype "passive"))
      (node (ref "X4") (pin "2") (pinfunction "GND_2") (pintype "passive"))
    )
    (net (code "66") (name "Net-(CHG-PadC)") (class "Default")
      (node (ref "CHG") (pin "C") (pinfunction "C_C") (pintype "passive"))
      (node (ref "R2") (pin "1") (pinfunction "1_1") (pintype "passive"))
    )
    (net (code "67") (name "Net-(D1-PadA)") (class "Default")
      (node (ref "D1") (pin "A") (pinfunction "A_A") (pintype "passive"))
      (node (ref "R14") (pin "1") (pinfunction "1_1") (pintype "passive"))
    )
    (net (code "68") (name "Net-(D3-PadA)") (class "Default")
      (node (ref "D3") (pin "A") (pinfunction "A_A") (pintype "passive"))
      (node (ref "R15") (pin "1") (pinfunction "1_1") (pintype "passive"))
    )
    (net (code "69") (name "Net-(D5-PadA)") (class "Default")
      (node (ref "D5") (pin "A") (pinfunction "A_A") (pintype "passive"))
      (node (ref "J7") (pin "1") (pinfunction "1_1") (pintype "passive"))
    )
    (net (code "70") (name "Net-(L-PadA)") (class "Default")
      (node (ref "L") (pin "A") (pinfunction "A_A") (pintype "passive"))
      (node (ref "R7") (pin "2") (pinfunction "2_2") (pintype "passive"))
    )
    (net (code "71") (name "Net-(U$4-PA00{slash}EINT0{slash}SERCOM1.0)") (class "Default")
      (node (ref "C2") (pin "1") (pinfunction "1_1") (pintype "passive"))
      (node (ref "U$4") (pin "1") (pinfunction "PA00/EINT0/SERCOM1.0_1") (pintype "bidirectional"))
      (node (ref "X2") (pin "P$1") (pinfunction "P$1_P$1") (pintype "bidirectional"))
    )
    (net (code "72") (name "Net-(U$4-PA01{slash}EINT1{slash}SERCOM1.1)") (class "Default")
      (node (ref "C4") (pin "1") (pinfunction "1_1") (pintype "passive"))
      (node (ref "U$4") (pin "2") (pinfunction "PA01/EINT1/SERCOM1.1_2") (pintype "bidirectional"))
      (node (ref "X2") (pin "P$2") (pinfunction "P$2_P$2") (pintype "bidirectional"))
    )
    (net (code "73") (name "Net-(U$4-VDDCORE)") (class "Default")
      (node (ref "C1") (pin "1") (pinfunction "1_1") (pintype "passive"))
      (node (ref "U$4") (pin "43") (pinfunction "VDDCORE_43") (pintype "power_in"))
    )
    (net (code "74") (name "Net-(U3-PROG)") (class "Default")
      (node (ref "R8") (pin "1") (pinfunction "1_1") (pintype "passive"))
      (node (ref "U3") (pin "5") (pinfunction "PROG_5") (pintype "input"))
    )
    (net (code "75") (name "Net-(U3-STAT)") (class "Default")
      (node (ref "R2") (pin "2") (pinfunction "2_2") (pintype "passive"))
      (node (ref "U3") (pin "1") (pinfunction "STAT_1") (pintype "output"))
    )
    (net (code "76") (name "Net-(U4-ANT)") (class "Default")
      (node (ref "JP2") (pin "1") (pinfunction "1_1") (pintype "passive"))
      (node (ref "U4") (pin "1P") (pinfunction "ANT_1P") (pintype "bidirectional"))
      (node (ref "X4") (pin "3") (pinfunction "SIGNAL_3") (pintype "passive"))
    )
    (net (code "77") (name "Net-(U8-1C)") (class "Default")
      (node (ref "J3") (pin "1") (pinfunction "1_1") (pintype "passive"))
      (node (ref "U8") (pin "16") (pinfunction "1C_16") (pintype "output"))
    )
    (net (code "78") (name "Net-(U8-2C)") (class "Default")
      (node (ref "J3") (pin "2") (pinfunction "2_2") (pintype "passive"))
      (node (ref "U8") (pin "15") (pinfunction "2C_15") (pintype "output"))
    )
    (net (code "79") (name "Net-(U8-3C)") (class "Default")
      (node (ref "J3") (pin "3") (pinfunction "3_3") (pintype "passive"))
      (node (ref "U8") (pin "14") (pinfunction "3C_14") (pintype "output"))
    )
    (net (code "80") (name "Net-(U8-4C)") (class "Default")
      (node (ref "J3") (pin "4") (pinfunction "4_4") (pintype "passive"))
      (node (ref "U8") (pin "13") (pinfunction "4C_13") (pintype "output"))
    )
    (net (code "81") (name "Net-(U9-1C)") (class "Default")
      (node (ref "J2") (pin "1") (pinfunction "1_1") (pintype "passive"))
      (node (ref "U9") (pin "16") (pinfunction "1C_16") (pintype "output"))
    )
    (net (code "82") (name "Net-(U9-2C)") (class "Default")
      (node (ref "J2") (pin "2") (pinfunction "2_2") (pintype "passive"))
      (node (ref "U9") (pin "15") (pinfunction "2C_15") (pintype "output"))
    )
    (net (code "83") (name "Net-(U9-3C)") (class "Default")
      (node (ref "J2") (pin "3") (pinfunction "3_3") (pintype "passive"))
      (node (ref "U9") (pin "14") (pinfunction "3C_14") (pintype "output"))
    )
    (net (code "84") (name "Net-(U9-4C)") (class "Default")
      (node (ref "J2") (pin "4") (pinfunction "4_4") (pintype "passive"))
      (node (ref "U9") (pin "13") (pinfunction "4C_13") (pintype "output"))
    )
    (net (code "85") (name "Net-(U10-COMP)") (class "Default")
      (node (ref "C17") (pin "1") (pinfunction "1_1") (pintype "passive"))
      (node (ref "U10") (pin "6") (pinfunction "COMP_6") (pintype "passive"))
    )
    (net (code "86") (name "Net-(U10-VL)") (class "Default")
      (node (ref "C6") (pin "1") (pinfunction "1_1") (pintype "passive"))
      (node (ref "U10") (pin "11") (pinfunction "VL_11") (pintype "passive"))
    )
    (net (code "87") (name "Net-(U11-1C)") (class "Default")
      (node (ref "J4") (pin "1") (pinfunction "1_1") (pintype "passive"))
      (node (ref "U11") (pin "16") (pinfunction "1C_16") (pintype "output"))
    )
    (net (code "88") (name "Net-(U11-2C)") (class "Default")
      (node (ref "J4") (pin "2") (pinfunction "2_2") (pintype "passive"))
      (node (ref "U11") (pin "15") (pinfunction "2C_15") (pintype "output"))
    )
    (net (code "89") (name "Net-(U11-3C)") (class "Default")
      (node (ref "J4") (pin "3") (pinfunction "3_3") (pintype "passive"))
      (node (ref "U11") (pin "14") (pinfunction "3C_14") (pintype "output"))
    )
    (net (code "90") (name "Net-(U11-4C)") (class "Default")
      (node (ref "J4") (pin "4") (pinfunction "4_4") (pintype "passive"))
      (node (ref "U11") (pin "13") (pinfunction "4C_13") (pintype "output"))
    )
    (net (code "91") (name "Net-(U12-1C)") (class "Default")
      (node (ref "J5") (pin "1") (pinfunction "1_1") (pintype "passive"))
      (node (ref "U12") (pin "16") (pinfunction "1C_16") (pintype "output"))
    )
    (net (code "92") (name "Net-(U12-2C)") (class "Default")
      (node (ref "J5") (pin "2") (pinfunction "2_2") (pintype "passive"))
      (node (ref "U12") (pin "15") (pinfunction "2C_15") (pintype "output"))
    )
    (net (code "93") (name "Net-(U12-3C)") (class "Default")
      (node (ref "J5") (pin "3") (pinfunction "3_3") (pintype "passive"))
      (node (ref "U12") (pin "14") (pinfunction "3C_14") (pintype "output"))
    )
    (net (code "94") (name "Net-(U12-4C)") (class "Default")
      (node (ref "J5") (pin "4") (pinfunction "4_4") (pintype "passive"))
      (node (ref "U12") (pin "13") (pinfunction "4C_13") (pintype "output"))
    )
    (net (code "95") (name "Net-(U13-1C)") (class "Default")
      (node (ref "J6") (pin "1") (pinfunction "1_1") (pintype "passive"))
      (node (ref "U13") (pin "16") (pinfunction "1C_16") (pintype "output"))
    )
    (net (code "96") (name "Net-(U13-2C)") (class "Default")
      (node (ref "J6") (pin "2") (pinfunction "2_2") (pintype "passive"))
      (node (ref "U13") (pin "15") (pinfunction "2C_15") (pintype "output"))
    )
    (net (code "97") (name "Net-(U13-3C)") (class "Default")
      (node (ref "J6") (pin "3") (pinfunction "3_3") (pintype "passive"))
      (node (ref "U13") (pin "14") (pinfunction "3C_14") (pintype "output"))
    )
    (net (code "98") (name "Net-(U13-4C)") (class "Default")
      (node (ref "J6") (pin "4") (pinfunction "4_4") (pintype "passive"))
      (node (ref "U13") (pin "13") (pinfunction "4C_13") (pintype "output"))
    )
    (net (code "99") (name "VBAT") (class "Default")
      (node (ref "C3") (pin "1") (pinfunction "1_1") (pintype "passive"))
      (node (ref "D2") (pin "A") (pinfunction "A_A") (pintype "passive"))
      (node (ref "R3") (pin "1") (pinfunction "1_1") (pintype "passive"))
      (node (ref "U3") (pin "3") (pinfunction "VBAT_3") (pintype "power_in"))
      (node (ref "X1") (pin "2") (pinfunction "2_2") (pintype "passive"))
    )
    (net (code "100") (name "VBUS") (class "Default")
      (node (ref "C13") (pin "1") (pinfunction "1_1") (pintype "passive"))
      (node (ref "C16") (pin "1") (pinfunction "1_1") (pintype "passive"))
      (node (ref "C19") (pin "1") (pinfunction "1_1") (pintype "passive"))
      (node (ref "C7") (pin "1") (pinfunction "1_1") (pintype "passive"))
      (node (ref "CHG") (pin "A") (pinfunction "A_A") (pintype "passive"))
      (node (ref "D2") (pin "C") (pinfunction "C_C") (pintype "passive"))
      (node (ref "D5") (pin "C") (pinfunction "C_C") (pintype "passive"))
      (node (ref "L1") (pin "1") (pinfunction "1_1") (pintype "passive"))
      (node (ref "U10") (pin "10") (pinfunction "IN_10") (pintype "power_in"))
      (node (ref "U3") (pin "4") (pinfunction "VDD_4") (pintype "power_in"))
      (node (ref "U6") (pin "1") (pinfunction "VI_1") (pintype "power_in"))
      (node (ref "U7") (pin "1") (pinfunction "VIN_1") (pintype "power_in"))
      (node (ref "X3") (pin "VBUS") (pinfunction "VBUS_VBUS") (pintype "power_in"))
    )
    (net (code "101") (name "unconnected-(C18-Pad2)") (class "Default")
      (node (ref "C18") (pin "2") (pinfunction "2_2") (pintype "passive"))
    )
    (net (code "102") (name "unconnected-(IC1A-OUT16-Pad21)") (class "Default")
      (node (ref "IC1") (pin "21") (pinfunction "OUT16_21") (pintype "open_collector"))
    )
    (net (code "103") (name "unconnected-(IC1A-OUT17-Pad22)") (class "Default")
      (node (ref "IC1") (pin "22") (pinfunction "OUT17_22") (pintype "open_collector"))
    )
    (net (code "104") (name "unconnected-(IC1A-OUT18-Pad23)") (class "Default")
      (node (ref "IC1") (pin "23") (pinfunction "OUT18_23") (pintype "open_collector"))
    )
    (net (code "105") (name "unconnected-(IC1A-OUT19-Pad24)") (class "Default")
      (node (ref "IC1") (pin "24") (pinfunction "OUT19_24") (pintype "open_collector"))
    )
    (net (code "106") (name "unconnected-(IC1A-OUT20-Pad25)") (class "Default")
      (node (ref "IC1") (pin "25") (pinfunction "OUT20_25") (pintype "open_collector"))
    )
    (net (code "107") (name "unconnected-(IC1A-OUT21-Pad26)") (class "Default")
      (node (ref "IC1") (pin "26") (pinfunction "OUT21_26") (pintype "open_collector"))
    )
    (net (code "108") (name "unconnected-(IC1A-OUT22-Pad27)") (class "Default")
      (node (ref "IC1") (pin "27") (pinfunction "OUT22_27") (pintype "open_collector"))
    )
    (net (code "109") (name "unconnected-(IC1A-OUT23-Pad28)") (class "Default")
      (node (ref "IC1") (pin "28") (pinfunction "OUT23_28") (pintype "open_collector"))
    )
    (net (code "110") (name "unconnected-(U$4-PA13{slash}I13{slash}I2C{slash}SERCOM2+4.1-Pad22)") (class "Default")
      (node (ref "U$4") (pin "22") (pinfunction "PA13/I13/I2C/SERCOM2+4.1_22") (pintype "bidirectional"))
    )
    (net (code "111") (name "unconnected-(U$4-PA27{slash}I15-Pad39)") (class "Default")
      (node (ref "U$4") (pin "39") (pinfunction "PA27/I15_39") (pintype "bidirectional"))
    )
    (net (code "112") (name "unconnected-(U$4-PA28{slash}I8-Pad41)") (class "Default")
      (node (ref "U$4") (pin "41") (pinfunction "PA28/I8_41") (pintype "bidirectional"))
    )
    (net (code "113") (name "unconnected-(U$4-PB03{slash}I3{slash}AIN11{slash}SERCOM5.1-Pad48)") (class "Default")
      (node (ref "U$4") (pin "48") (pinfunction "PB03/I3/AIN11/SERCOM5.1_48") (pintype "bidirectional"))
    )
    (net (code "114") (name "unconnected-(U2-{slash}HOLD(IO3)-Pad7)") (class "Default")
      (node (ref "U2") (pin "7") (pinfunction "/HOLD(IO3)_7") (pintype "bidirectional"))
    )
    (net (code "115") (name "unconnected-(U2-{slash}WP(IO2)-Pad3)") (class "Default")
      (node (ref "U2") (pin "3") (pinfunction "/WP(IO2)_3") (pintype "bidirectional"))
    )
    (net (code "116") (name "unconnected-(U4-DIO4-Pad4P)") (class "Default")
      (node (ref "U4") (pin "4P") (pinfunction "DIO4_4P") (pintype "bidirectional"))
    )
    (net (code "117") (name "unconnected-(U5-GPIO-Pad6)") (class "Default")
      (node (ref "U5") (pin "6") (pinfunction "GPIO_6") (pintype "bidirectional"))
    )
    (net (code "118") (name "unconnected-(U7-EN-Pad3)") (class "Default")
      (node (ref "U7") (pin "3") (pinfunction "EN_3") (pintype "input"))
    )
    (net (code "119") (name "unconnected-(U7-NC-Pad4)") (class "Default")
      (node (ref "U7") (pin "4") (pinfunction "NC_4") (pintype "passive"))
    )
    (net (code "120") (name "unconnected-(U8-5B-Pad5)") (class "Default")
      (node (ref "U8") (pin "5") (pinfunction "5B_5") (pintype "input"))
    )
    (net (code "121") (name "unconnected-(U8-5C-Pad12)") (class "Default")
      (node (ref "U8") (pin "12") (pinfunction "5C_12") (pintype "output"))
    )
    (net (code "122") (name "unconnected-(U8-6B-Pad6)") (class "Default")
      (node (ref "U8") (pin "6") (pinfunction "6B_6") (pintype "input"))
    )
    (net (code "123") (name "unconnected-(U8-6C-Pad11)") (class "Default")
      (node (ref "U8") (pin "11") (pinfunction "6C_11") (pintype "output"))
    )
    (net (code "124") (name "unconnected-(U8-7B-Pad7)") (class "Default")
      (node (ref "U8") (pin "7") (pinfunction "7B_7") (pintype "input"))
    )
    (net (code "125") (name "unconnected-(U8-7C-Pad10)") (class "Default")
      (node (ref "U8") (pin "10") (pinfunction "7C_10") (pintype "output"))
    )
    (net (code "126") (name "unconnected-(U8-COM-Pad9)") (class "Default")
      (node (ref "U8") (pin "9") (pinfunction "COM_9") (pintype "bidirectional"))
    )
    (net (code "127") (name "unconnected-(U9-5B-Pad5)") (class "Default")
      (node (ref "U9") (pin "5") (pinfunction "5B_5") (pintype "input"))
    )
    (net (code "128") (name "unconnected-(U9-5C-Pad12)") (class "Default")
      (node (ref "U9") (pin "12") (pinfunction "5C_12") (pintype "output"))
    )
    (net (code "129") (name "unconnected-(U9-6B-Pad6)") (class "Default")
      (node (ref "U9") (pin "6") (pinfunction "6B_6") (pintype "input"))
    )
    (net (code "130") (name "unconnected-(U9-6C-Pad11)") (class "Default")
      (node (ref "U9") (pin "11") (pinfunction "6C_11") (pintype "output"))
    )
    (net (code "131") (name "unconnected-(U9-7B-Pad7)") (class "Default")
      (node (ref "U9") (pin "7") (pinfunction "7B_7") (pintype "input"))
    )
    (net (code "132") (name "unconnected-(U9-7C-Pad10)") (class "Default")
      (node (ref "U9") (pin "10") (pinfunction "7C_10") (pintype "output"))
    )
    (net (code "133") (name "unconnected-(U9-COM-Pad9)") (class "Default")
      (node (ref "U9") (pin "9") (pinfunction "COM_9") (pintype "bidirectional"))
    )
    (net (code "134") (name "unconnected-(U10-~{SHDN}-Pad5)") (class "Default")
      (node (ref "U10") (pin "5") (pinfunction "~{SHDN}_5") (pintype "input"))
    )
    (net (code "135") (name "unconnected-(U11-5B-Pad5)") (class "Default")
      (node (ref "U11") (pin "5") (pinfunction "5B_5") (pintype "input"))
    )
    (net (code "136") (name "unconnected-(U11-5C-Pad12)") (class "Default")
      (node (ref "U11") (pin "12") (pinfunction "5C_12") (pintype "output"))
    )
    (net (code "137") (name "unconnected-(U11-6B-Pad6)") (class "Default")
      (node (ref "U11") (pin "6") (pinfunction "6B_6") (pintype "input"))
    )
    (net (code "138") (name "unconnected-(U11-6C-Pad11)") (class "Default")
      (node (ref "U11") (pin "11") (pinfunction "6C_11") (pintype "output"))
    )
    (net (code "139") (name "unconnected-(U11-7B-Pad7)") (class "Default")
      (node (ref "U11") (pin "7") (pinfunction "7B_7") (pintype "input"))
    )
    (net (code "140") (name "unconnected-(U11-7C-Pad10)") (class "Default")
      (node (ref "U11") (pin "10") (pinfunction "7C_10") (pintype "output"))
    )
    (net (code "141") (name "unconnected-(U11-COM-Pad9)") (class "Default")
      (node (ref "U11") (pin "9") (pinfunction "COM_9") (pintype "bidirectional"))
    )
    (net (code "142") (name "unconnected-(U12-5B-Pad5)") (class "Default")
      (node (ref "U12") (pin "5") (pinfunction "5B_5") (pintype "input"))
    )
    (net (code "143") (name "unconnected-(U12-5C-Pad12)") (class "Default")
      (node (ref "U12") (pin "12") (pinfunction "5C_12") (pintype "output"))
    )
    (net (code "144") (name "unconnected-(U12-6B-Pad6)") (class "Default")
      (node (ref "U12") (pin "6") (pinfunction "6B_6") (pintype "input"))
    )
    (net (code "145") (name "unconnected-(U12-6C-Pad11)") (class "Default")
      (node (ref "U12") (pin "11") (pinfunction "6C_11") (pintype "output"))
    )
    (net (code "146") (name "unconnected-(U12-7B-Pad7)") (class "Default")
      (node (ref "U12") (pin "7") (pinfunction "7B_7") (pintype "input"))
    )
    (net (code "147") (name "unconnected-(U12-7C-Pad10)") (class "Default")
      (node (ref "U12") (pin "10") (pinfunction "7C_10") (pintype "output"))
    )
    (net (code "148") (name "unconnected-(U12-COM-Pad9)") (class "Default")
      (node (ref "U12") (pin "9") (pinfunction "COM_9") (pintype "bidirectional"))
    )
    (net (code "149") (name "unconnected-(U13-5B-Pad5)") (class "Default")
      (node (ref "U13") (pin "5") (pinfunction "5B_5") (pintype "input"))
    )
    (net (code "150") (name "unconnected-(U13-5C-Pad12)") (class "Default")
      (node (ref "U13") (pin "12") (pinfunction "5C_12") (pintype "output"))
    )
    (net (code "151") (name "unconnected-(U13-6B-Pad6)") (class "Default")
      (node (ref "U13") (pin "6") (pinfunction "6B_6") (pintype "input"))
    )
    (net (code "152") (name "unconnected-(U13-6C-Pad11)") (class "Default")
      (node (ref "U13") (pin "11") (pinfunction "6C_11") (pintype "output"))
    )
    (net (code "153") (name "unconnected-(U13-7B-Pad7)") (class "Default")
      (node (ref "U13") (pin "7") (pinfunction "7B_7") (pintype "input"))
    )
    (net (code "154") (name "unconnected-(U13-7C-Pad10)") (class "Default")
      (node (ref "U13") (pin "10") (pinfunction "7C_10") (pintype "output"))
    )
    (net (code "155") (name "unconnected-(U13-COM-Pad9)") (class "Default")
      (node (ref "U13") (pin "9") (pinfunction "COM_9") (pintype "bidirectional"))
    )
    (net (code "156") (name "unconnected-(X3-PadID)") (class "Default")
      (node (ref "X3") (pin "ID") (pinfunction "ID_ID") (pintype "bidirectional"))
    )
  )
)
